# DC30_Cnet_Cow-A-Bunga_SAO_Panel.net
KiCad netlist of a schematic drawn in EAGLE
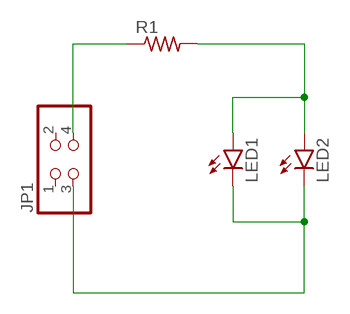
[diagram p0: schematic, sheet 1]

(export (version "E")
  (design (tool "Eeschema 10.0.6"))
  (components
    (comp (ref "JP1")
      (value "PINHD-2X2")
      (footprint "eagle-import:2X02")
      (libsource (lib "eagle-import") (part "PINHD-2X2"))
    )
    (comp (ref "LED1")
      (value "LED3MM")
      (footprint "eagle-import:LED3MM")
      (libsource (lib "eagle-import") (part "LED3MM"))
    )
    (comp (ref "LED2")
      (value "LED3MM")
      (footprint "eagle-import:LED3MM")
      (libsource (lib "eagle-import") (part "LED3MM"))
    )
    (comp (ref "R1")
      (value "R-US_R0805")
      (footprint "eagle-import:R0805")
      (libsource (lib "eagle-import") (part "R-US_R0805"))
    )
  )
  (nets
    (net (code "1") (name "Net-(JP1-Pad4)") (class "Default")
      (node (ref "JP1") (pin "4") (pinfunction "4_4") (pintype "passive"))
      (node (ref "R1") (pin "1") (pinfunction "1_1") (pintype "passive"))
    )
    (net (code "2") (name "Net-(LED1-C)") (class "Default")
      (node (ref "JP1") (pin "3") (pinfunction "3_3") (pintype "passive"))
      (node (ref "LED1") (pin "K") (pinfunction "C_K") (pintype "passive"))
      (node (ref "LED2") (pin "K") (pinfunction "C_K") (pintype "passive"))
    )
    (net (code "3") (name "Net-(LED1-PadA)") (class "Default")
      (node (ref "LED1") (pin "A") (pinfunction "A_A") (pintype "passive"))
      (node (ref "LED2") (pin "A") (pinfunction "A_A") (pintype "passive"))
      (node (ref "R1") (pin "2") (pinfunction "2_2") (pintype "passive"))
    )
    (net (code "4") (name "unconnected-(JP1-Pad1)") (class "Default")
      (node (ref "JP1") (pin "1") (pinfunction "1_1") (pintype "passive"))
    )
    (net (code "5") (name "unconnected-(JP1-Pad2)") (class "Default")
      (node (ref "JP1") (pin "2") (pinfunction "2_2") (pintype "passive"))
    )
  )
)
